# MULTIWII.net
KiCad netlist of a schematic drawn in EAGLE
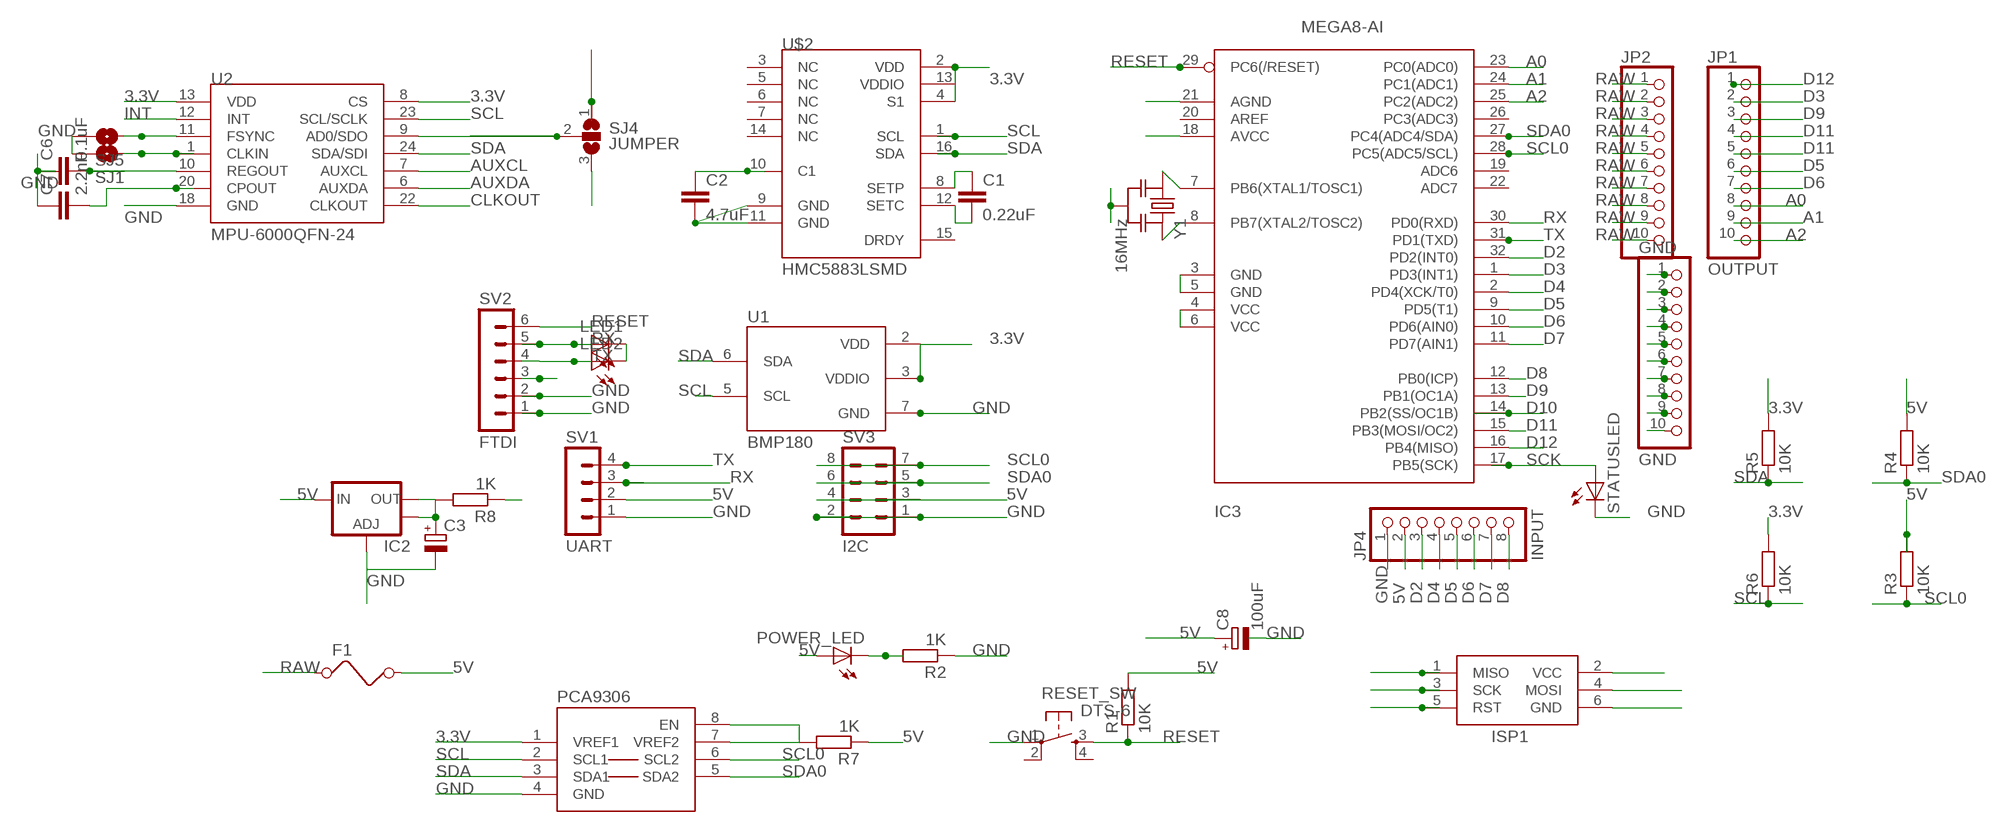
[diagram p0: schematic, sheet 1]

(export (version "E")
  (design (tool "Eeschema 10.0.6"))
  (components
    (comp (ref "C1")
      (value "0.22uF")
      (footprint "eagle-import:C0805")
      (libsource (lib "eagle-import") (part "C-EUC0805"))
    )
    (comp (ref "C2")
      (value "4.7uF")
      (footprint "eagle-import:C0805")
      (libsource (lib "eagle-import") (part "C-EUC0805"))
    )
    (comp (ref "C3")
      (value "CPOL-EUA/3216-18R")
      (footprint "eagle-import:A_3216-18R")
      (libsource (lib "eagle-import") (part "CPOL-EUA/3216-18R"))
    )
    (comp (ref "C6")
      (value "0.1uF")
      (footprint "eagle-import:C0805")
      (libsource (lib "eagle-import") (part "C-EUC0805"))
    )
    (comp (ref "C7")
      (value "2.2nF")
      (footprint "eagle-import:C0805")
      (libsource (lib "eagle-import") (part "C-EUC0805"))
    )
    (comp (ref "C8")
      (value "100uF")
      (footprint "eagle-import:CT7343")
      (libsource (lib "eagle-import") (part "CPOL-EUCT7343"))
    )
    (comp (ref "F1")
      (value "FUSEF")
      (footprint "eagle-import:1812")
      (libsource (lib "eagle-import") (part "FUSEF"))
    )
    (comp (ref "GND")
      (value "GND")
      (footprint "eagle-import:1X10")
      (libsource (lib "eagle-import") (part "PINHD-1X10"))
    )
    (comp (ref "IC2")
      (value "V_REG_LM1117SOT223")
      (footprint "eagle-import:SOT223")
      (libsource (lib "eagle-import") (part "V_REG_LM1117SOT223"))
    )
    (comp (ref "IC3")
      (value "MEGA8-AI")
      (footprint "eagle-import:TQFP32-08")
      (libsource (lib "eagle-import") (part "MEGA8-AI"))
    )
    (comp (ref "ISP1")
      (value "AVRISP-6")
      (footprint "eagle-import:AVRISP")
      (libsource (lib "eagle-import") (part "AVRISP-6"))
    )
    (comp (ref "JP1")
      (value "OUTPUT")
      (footprint "eagle-import:1X10")
      (libsource (lib "eagle-import") (part "PINHD-1X10"))
    )
    (comp (ref "JP2")
      (value "PINHD-1X10")
      (footprint "eagle-import:1X10")
      (libsource (lib "eagle-import") (part "PINHD-1X10"))
    )
    (comp (ref "JP4")
      (value "INPUT")
      (footprint "eagle-import:1X08")
      (libsource (lib "eagle-import") (part "PINHD-1X8"))
    )
    (comp (ref "LED1")
      (value "LEDCHIPLED_0805")
      (footprint "eagle-import:CHIPLED_0805")
      (libsource (lib "eagle-import") (part "LEDCHIPLED_0805"))
    )
    (comp (ref "LED2")
      (value "LEDCHIPLED_0805")
      (footprint "eagle-import:CHIPLED_0805")
      (libsource (lib "eagle-import") (part "LEDCHIPLED_0805"))
    )
    (comp (ref "PCA9306")
      (value "PCA9306")
      (footprint "eagle-import:PSOP-8")
      (libsource (lib "eagle-import") (part "PCA9306"))
    )
    (comp (ref "POWER_LED")
      (value "LEDCHIPLED_1206")
      (footprint "eagle-import:CHIPLED_1206")
      (libsource (lib "eagle-import") (part "LEDCHIPLED_1206"))
    )
    (comp (ref "R1")
      (value "10K")
      (footprint "eagle-import:M0805")
      (libsource (lib "eagle-import") (part "R-EU_M0805"))
    )
    (comp (ref "R2")
      (value "1K")
      (footprint "eagle-import:M0805")
      (libsource (lib "eagle-import") (part "R-EU_M0805"))
    )
    (comp (ref "R3")
      (value "10K")
      (footprint "eagle-import:M0805")
      (libsource (lib "eagle-import") (part "R-EU_M0805"))
    )
    (comp (ref "R4")
      (value "10K")
      (footprint "eagle-import:M0805")
      (libsource (lib "eagle-import") (part "R-EU_M0805"))
    )
    (comp (ref "R5")
      (value "10K")
      (footprint "eagle-import:M0805")
      (libsource (lib "eagle-import") (part "R-EU_M0805"))
    )
    (comp (ref "R6")
      (value "10K")
      (footprint "eagle-import:M0805")
      (libsource (lib "eagle-import") (part "R-EU_M0805"))
    )
    (comp (ref "R7")
      (value "1K")
      (footprint "eagle-import:M0805")
      (libsource (lib "eagle-import") (part "R-EU_M0805"))
    )
    (comp (ref "R8")
      (value "1K")
      (footprint "eagle-import:M0805")
      (libsource (lib "eagle-import") (part "R-EU_M0805"))
    )
    (comp (ref "RESET_SW")
      (value "DTS-6")
      (footprint "eagle-import:DTS-6")
      (libsource (lib "eagle-import") (part "DTS-6"))
    )
    (comp (ref "SJ1")
      (value "SOLDERJUMPERNC")
      (footprint "eagle-import:SJ_2S")
      (libsource (lib "eagle-import") (part "SOLDERJUMPERNC"))
    )
    (comp (ref "SJ4")
      (value "JUMPER")
      (footprint "eagle-import:SJ_2")
      (libsource (lib "eagle-import") (part "SJ2W"))
    )
    (comp (ref "SJ5")
      (value "SOLDERJUMPERNC")
      (footprint "eagle-import:SJ_2S")
      (libsource (lib "eagle-import") (part "SOLDERJUMPERNC"))
    )
    (comp (ref "STATUSLED")
      (value "LEDCHIP-LED0805")
      (footprint "eagle-import:CHIP-LED0805")
      (libsource (lib "eagle-import") (part "LEDCHIP-LED0805"))
    )
    (comp (ref "SV1")
      (value "UART")
      (footprint "eagle-import:MA04-1")
      (libsource (lib "eagle-import") (part "MA04-1"))
    )
    (comp (ref "SV2")
      (value "FTDI")
      (footprint "eagle-import:MA06-1")
      (libsource (lib "eagle-import") (part "MA06-1"))
    )
    (comp (ref "SV3")
      (value "I2C")
      (footprint "eagle-import:MA04-2")
      (libsource (lib "eagle-import") (part "MA04-2"))
    )
    (comp (ref "U$2")
      (value "HMC5883LSMD")
      (footprint "eagle-import:16LPCC")
      (libsource (lib "eagle-import") (part "HMC5883LSMD"))
    )
    (comp (ref "U1")
      (value "BMP180")
      (footprint "eagle-import:BMP180")
      (libsource (lib "eagle-import") (part "BMP180"))
    )
    (comp (ref "U2")
      (value "MPU-6000QFN-24")
      (footprint "eagle-import:QFN-24-TESTING")
      (libsource (lib "eagle-import") (part "MPU-6000QFN-24"))
    )
    (comp (ref "Y1")
      (value "16MHz")
      (footprint "eagle-import:RESONATOR_MURATA3")
      (libsource (lib "eagle-import") (part "RESONATOR-MURATACSTCR_G"))
    )
  )
  (nets
    (net (code "1") (name "3.3V") (class "Default")
      (node (ref "PCA9306") (pin "1") (pinfunction "VREF1_1") (pintype "bidirectional"))
      (node (ref "R5") (pin "2") (pinfunction "2_2") (pintype "passive"))
      (node (ref "R6") (pin "2") (pinfunction "2_2") (pintype "passive"))
      (node (ref "R8") (pin "1") (pinfunction "1_1") (pintype "passive"))
      (node (ref "SJ4") (pin "1") (pinfunction "1_1") (pintype "passive"))
      (node (ref "U$2") (pin "13") (pinfunction "VDDIO_13") (pintype "bidirectional"))
      (node (ref "U$2") (pin "2") (pinfunction "VDD_2") (pintype "bidirectional"))
      (node (ref "U$2") (pin "4") (pinfunction "S1_4") (pintype "bidirectional"))
      (node (ref "U1") (pin "2") (pinfunction "VDD_2") (pintype "power_in"))
      (node (ref "U1") (pin "3") (pinfunction "VDDIO_3") (pintype "power_in"))
      (node (ref "U2") (pin "13") (pinfunction "VDD_13") (pintype "bidirectional"))
      (node (ref "U2") (pin "8") (pinfunction "CS_8") (pintype "bidirectional"))
    )
    (net (code "2") (name "5V") (class "Default")
      (node (ref "C8") (pin "+") (pinfunction "+_+") (pintype "passive"))
      (node (ref "F1") (pin "2") (pinfunction "2_2") (pintype "passive"))
      (node (ref "IC2") (pin "3") (pinfunction "IN_3") (pintype "input"))
      (node (ref "IC3") (pin "18") (pinfunction "AVCC_18") (pintype "bidirectional"))
      (node (ref "IC3") (pin "4") (pinfunction "VCC_4") (pintype "bidirectional"))
      (node (ref "IC3") (pin "6") (pinfunction "VCC_6") (pintype "bidirectional"))
      (node (ref "ISP1") (pin "2") (pinfunction "VCC_2") (pintype "power_in"))
      (node (ref "JP4") (pin "2") (pinfunction "2_2") (pintype "passive"))
      (node (ref "POWER_LED") (pin "A") (pinfunction "A_A") (pintype "passive"))
      (node (ref "R1") (pin "2") (pinfunction "2_2") (pintype "passive"))
      (node (ref "R3") (pin "2") (pinfunction "2_2") (pintype "passive"))
      (node (ref "R4") (pin "2") (pinfunction "2_2") (pintype "passive"))
      (node (ref "R7") (pin "1") (pinfunction "1_1") (pintype "passive"))
      (node (ref "SV1") (pin "2") (pinfunction "2_2") (pintype "passive"))
      (node (ref "SV3") (pin "3") (pinfunction "3_3") (pintype "passive"))
      (node (ref "SV3") (pin "4") (pinfunction "4_4") (pintype "passive"))
    )
    (net (code "3") (name "A0") (class "Default")
      (node (ref "IC3") (pin "23") (pinfunction "PC0(ADC0)_23") (pintype "bidirectional"))
      (node (ref "JP1") (pin "8") (pinfunction "8_8") (pintype "passive"))
    )
    (net (code "4") (name "A1") (class "Default")
      (node (ref "IC3") (pin "24") (pinfunction "PC1(ADC1)_24") (pintype "bidirectional"))
      (node (ref "JP1") (pin "9") (pinfunction "9_9") (pintype "passive"))
    )
    (net (code "5") (name "A2") (class "Default")
      (node (ref "IC3") (pin "25") (pinfunction "PC2(ADC2)_25") (pintype "bidirectional"))
      (node (ref "JP1") (pin "10") (pinfunction "10_10") (pintype "passive"))
    )
    (net (code "6") (name "AUXCL") (class "Default")
      (node (ref "U2") (pin "7") (pinfunction "AUXCL_7") (pintype "bidirectional"))
    )
    (net (code "7") (name "AUXDA") (class "Default")
      (node (ref "U2") (pin "6") (pinfunction "AUXDA_6") (pintype "bidirectional"))
    )
    (net (code "8") (name "CLKOUT") (class "Default")
      (node (ref "U2") (pin "22") (pinfunction "CLKOUT_22") (pintype "bidirectional"))
    )
    (net (code "9") (name "D2") (class "Default")
      (node (ref "IC3") (pin "32") (pinfunction "PD2(INT0)_32") (pintype "bidirectional"))
      (node (ref "JP4") (pin "3") (pinfunction "3_3") (pintype "passive"))
    )
    (net (code "10") (name "D3") (class "Default")
      (node (ref "IC3") (pin "1") (pinfunction "PD3(INT1)_1") (pintype "bidirectional"))
      (node (ref "JP1") (pin "2") (pinfunction "2_2") (pintype "passive"))
    )
    (net (code "11") (name "D4") (class "Default")
      (node (ref "IC3") (pin "2") (pinfunction "PD4(XCK/T0)_2") (pintype "bidirectional"))
      (node (ref "JP4") (pin "4") (pinfunction "4_4") (pintype "passive"))
    )
    (net (code "12") (name "D5") (class "Default")
      (node (ref "IC3") (pin "9") (pinfunction "PD5(T1)_9") (pintype "bidirectional"))
      (node (ref "JP1") (pin "6") (pinfunction "6_6") (pintype "passive"))
      (node (ref "JP4") (pin "5") (pinfunction "5_5") (pintype "passive"))
    )
    (net (code "13") (name "D6") (class "Default")
      (node (ref "IC3") (pin "10") (pinfunction "PD6(AIN0)_10") (pintype "bidirectional"))
      (node (ref "JP1") (pin "7") (pinfunction "7_7") (pintype "passive"))
      (node (ref "JP4") (pin "6") (pinfunction "6_6") (pintype "passive"))
    )
    (net (code "14") (name "D7") (class "Default")
      (node (ref "IC3") (pin "11") (pinfunction "PD7(AIN1)_11") (pintype "bidirectional"))
      (node (ref "JP4") (pin "7") (pinfunction "7_7") (pintype "passive"))
    )
    (net (code "15") (name "D8") (class "Default")
      (node (ref "IC3") (pin "12") (pinfunction "PB0(ICP)_12") (pintype "bidirectional"))
      (node (ref "JP4") (pin "8") (pinfunction "8_8") (pintype "passive"))
    )
    (net (code "16") (name "D9") (class "Default")
      (node (ref "IC3") (pin "13") (pinfunction "PB1(OC1A)_13") (pintype "bidirectional"))
      (node (ref "JP1") (pin "3") (pinfunction "3_3") (pintype "passive"))
    )
    (net (code "17") (name "D10") (class "Default")
      (node (ref "IC3") (pin "14") (pinfunction "PB2(SS/OC1B)_14") (pintype "bidirectional"))
      (node (ref "JP1") (pin "4") (pinfunction "4_4") (pintype "passive"))
    )
    (net (code "18") (name "D11") (class "Default")
      (node (ref "IC3") (pin "15") (pinfunction "PB3(MOSI/OC2)_15") (pintype "bidirectional"))
      (node (ref "ISP1") (pin "4") (pinfunction "MOSI_4") (pintype "output"))
      (node (ref "JP1") (pin "5") (pinfunction "5_5") (pintype "passive"))
    )
    (net (code "19") (name "D12") (class "Default")
      (node (ref "IC3") (pin "16") (pinfunction "PB4(MISO)_16") (pintype "bidirectional"))
      (node (ref "ISP1") (pin "1") (pinfunction "MISO_1") (pintype "input"))
      (node (ref "JP1") (pin "1") (pinfunction "1_1") (pintype "passive"))
    )
    (net (code "20") (name "GND") (class "Default")
      (node (ref "C2") (pin "2") (pinfunction "2_2") (pintype "passive"))
      (node (ref "C3") (pin "-") (pinfunction "-_-") (pintype "passive"))
      (node (ref "C6") (pin "1") (pinfunction "1_1") (pintype "passive"))
      (node (ref "C7") (pin "1") (pinfunction "1_1") (pintype "passive"))
      (node (ref "C8") (pin "-") (pinfunction "-_-") (pintype "passive"))
      (node (ref "GND") (pin "1") (pinfunction "1_1") (pintype "passive"))
      (node (ref "GND") (pin "10") (pinfunction "10_10") (pintype "passive"))
      (node (ref "GND") (pin "2") (pinfunction "2_2") (pintype "passive"))
      (node (ref "GND") (pin "3") (pinfunction "3_3") (pintype "passive"))
      (node (ref "GND") (pin "4") (pinfunction "4_4") (pintype "passive"))
      (node (ref "GND") (pin "5") (pinfunction "5_5") (pintype "passive"))
      (node (ref "GND") (pin "6") (pinfunction "6_6") (pintype "passive"))
      (node (ref "GND") (pin "7") (pinfunction "7_7") (pintype "passive"))
      (node (ref "GND") (pin "8") (pinfunction "8_8") (pintype "passive"))
      (node (ref "GND") (pin "9") (pinfunction "9_9") (pintype "passive"))
      (node (ref "IC2") (pin "1") (pinfunction "ADJ_1") (pintype "input"))
      (node (ref "IC3") (pin "21") (pinfunction "AGND_21") (pintype "bidirectional"))
      (node (ref "IC3") (pin "3") (pinfunction "GND_3") (pintype "bidirectional"))
      (node (ref "IC3") (pin "5") (pinfunction "GND_5") (pintype "bidirectional"))
      (node (ref "ISP1") (pin "6") (pinfunction "GND_6") (pintype "power_in"))
      (node (ref "JP4") (pin "1") (pinfunction "1_1") (pintype "passive"))
      (node (ref "LED1") (pin "C") (pinfunction "C_C") (pintype "passive"))
      (node (ref "LED2") (pin "C") (pinfunction "C_C") (pintype "passive"))
      (node (ref "PCA9306") (pin "4") (pinfunction "GND_4") (pintype "bidirectional"))
      (node (ref "R2") (pin "1") (pinfunction "1_1") (pintype "passive"))
      (node (ref "RESET_SW") (pin "1") (pinfunction "1_1") (pintype "passive"))
      (node (ref "SJ1") (pin "2") (pinfunction "2_2") (pintype "passive"))
      (node (ref "SJ4") (pin "3") (pinfunction "3_3") (pintype "passive"))
      (node (ref "SJ5") (pin "2") (pinfunction "2_2") (pintype "passive"))
      (node (ref "STATUSLED") (pin "C") (pinfunction "C_C") (pintype "passive"))
      (node (ref "SV1") (pin "1") (pinfunction "1_1") (pintype "passive"))
      (node (ref "SV2") (pin "1") (pinfunction "1_1") (pintype "passive"))
      (node (ref "SV2") (pin "2") (pinfunction "2_2") (pintype "passive"))
      (node (ref "SV3") (pin "1") (pinfunction "1_1") (pintype "passive"))
      (node (ref "SV3") (pin "2") (pinfunction "2_2") (pintype "passive"))
      (node (ref "U$2") (pin "11") (pinfunction "GND_11") (pintype "bidirectional"))
      (node (ref "U$2") (pin "9") (pinfunction "GND_9") (pintype "bidirectional"))
      (node (ref "U1") (pin "7") (pinfunction "GND_7") (pintype "power_in"))
      (node (ref "U2") (pin "18") (pinfunction "GND_18") (pintype "bidirectional"))
      (node (ref "Y1") (pin "2") (pinfunction "2_2") (pintype "passive"))
    )
    (net (code "21") (name "INT") (class "Default")
      (node (ref "U2") (pin "12") (pinfunction "INT_12") (pintype "bidirectional"))
    )
    (net (code "22") (name "Net-(C3-Pad+)") (class "Default")
      (node (ref "C3") (pin "+") (pinfunction "+_+") (pintype "passive"))
      (node (ref "IC2") (pin "2") (pinfunction "OUT_2") (pintype "output"))
      (node (ref "IC2") (pin "4") (pinfunction "OUT_4") (pintype "output"))
      (node (ref "R8") (pin "2") (pinfunction "2_2") (pintype "passive"))
    )
    (net (code "23") (name "Net-(IC3-PB6(XTAL1{slash}TOSC1))") (class "Default")
      (node (ref "IC3") (pin "7") (pinfunction "PB6(XTAL1/TOSC1)_7") (pintype "bidirectional"))
      (node (ref "Y1") (pin "1") (pinfunction "1_1") (pintype "passive"))
    )
    (net (code "24") (name "Net-(IC3-PB7(XTAL2{slash}TOSC2))") (class "Default")
      (node (ref "IC3") (pin "8") (pinfunction "PB7(XTAL2/TOSC2)_8") (pintype "bidirectional"))
      (node (ref "Y1") (pin "3") (pinfunction "3_3") (pintype "passive"))
    )
    (net (code "25") (name "Net-(PCA9306-EN)") (class "Default")
      (node (ref "PCA9306") (pin "7") (pinfunction "VREF2_7") (pintype "bidirectional"))
      (node (ref "PCA9306") (pin "8") (pinfunction "EN_8") (pintype "bidirectional"))
      (node (ref "R7") (pin "2") (pinfunction "2_2") (pintype "passive"))
    )
    (net (code "26") (name "Net-(POWER_LED-PadC)") (class "Default")
      (node (ref "POWER_LED") (pin "C") (pinfunction "C_C") (pintype "passive"))
      (node (ref "R2") (pin "2") (pinfunction "2_2") (pintype "passive"))
    )
    (net (code "27") (name "Net-(U$2-C1)") (class "Default")
      (node (ref "C2") (pin "1") (pinfunction "1_1") (pintype "passive"))
      (node (ref "U$2") (pin "10") (pinfunction "C1_10") (pintype "bidirectional"))
    )
    (net (code "28") (name "Net-(U$2-SETC)") (class "Default")
      (node (ref "C1") (pin "2") (pinfunction "2_2") (pintype "passive"))
      (node (ref "U$2") (pin "12") (pinfunction "SETC_12") (pintype "bidirectional"))
    )
    (net (code "29") (name "Net-(U$2-SETP)") (class "Default")
      (node (ref "C1") (pin "1") (pinfunction "1_1") (pintype "passive"))
      (node (ref "U$2") (pin "8") (pinfunction "SETP_8") (pintype "bidirectional"))
    )
    (net (code "30") (name "Net-(U2-AD0{slash}SDO)") (class "Default")
      (node (ref "SJ4") (pin "2") (pinfunction "2_2") (pintype "passive"))
      (node (ref "U2") (pin "9") (pinfunction "AD0/SDO_9") (pintype "bidirectional"))
    )
    (net (code "31") (name "Net-(U2-CLKIN)") (class "Default")
      (node (ref "SJ1") (pin "1") (pinfunction "1_1") (pintype "passive"))
      (node (ref "U2") (pin "1") (pinfunction "CLKIN_1") (pintype "bidirectional"))
    )
    (net (code "32") (name "Net-(U2-CPOUT)") (class "Default")
      (node (ref "C7") (pin "2") (pinfunction "2_2") (pintype "passive"))
      (node (ref "U2") (pin "20") (pinfunction "CPOUT_20") (pintype "bidirectional"))
    )
    (net (code "33") (name "Net-(U2-FSYNC)") (class "Default")
      (node (ref "SJ5") (pin "1") (pinfunction "1_1") (pintype "passive"))
      (node (ref "U2") (pin "11") (pinfunction "FSYNC_11") (pintype "bidirectional"))
    )
    (net (code "34") (name "Net-(U2-REGOUT)") (class "Default")
      (node (ref "C6") (pin "2") (pinfunction "2_2") (pintype "passive"))
      (node (ref "U2") (pin "10") (pinfunction "REGOUT_10") (pintype "bidirectional"))
    )
    (net (code "35") (name "RAW") (class "Default")
      (node (ref "F1") (pin "1") (pinfunction "1_1") (pintype "passive"))
      (node (ref "JP2") (pin "1") (pinfunction "1_1") (pintype "passive"))
      (node (ref "JP2") (pin "10") (pinfunction "10_10") (pintype "passive"))
      (node (ref "JP2") (pin "2") (pinfunction "2_2") (pintype "passive"))
      (node (ref "JP2") (pin "3") (pinfunction "3_3") (pintype "passive"))
      (node (ref "JP2") (pin "4") (pinfunction "4_4") (pintype "passive"))
      (node (ref "JP2") (pin "5") (pinfunction "5_5") (pintype "passive"))
      (node (ref "JP2") (pin "6") (pinfunction "6_6") (pintype "passive"))
      (node (ref "JP2") (pin "7") (pinfunction "7_7") (pintype "passive"))
      (node (ref "JP2") (pin "8") (pinfunction "8_8") (pintype "passive"))
      (node (ref "JP2") (pin "9") (pinfunction "9_9") (pintype "passive"))
      (node (ref "SV2") (pin "3") (pinfunction "3_3") (pintype "passive"))
    )
    (net (code "36") (name "RESET") (class "Default")
      (node (ref "IC3") (pin "29") (pinfunction "PC6(/RESET)_29") (pintype "bidirectional"))
      (node (ref "ISP1") (pin "5") (pinfunction "RST_5") (pintype "output"))
      (node (ref "R1") (pin "1") (pinfunction "1_1") (pintype "passive"))
      (node (ref "RESET_SW") (pin "3") (pinfunction "3_3") (pintype "passive"))
      (node (ref "SV2") (pin "6") (pinfunction "6_6") (pintype "passive"))
    )
    (net (code "37") (name "RX") (class "Default")
      (node (ref "IC3") (pin "30") (pinfunction "PD0(RXD)_30") (pintype "bidirectional"))
      (node (ref "LED1") (pin "A") (pinfunction "A_A") (pintype "passive"))
      (node (ref "SV1") (pin "3") (pinfunction "3_3") (pintype "passive"))
      (node (ref "SV2") (pin "5") (pinfunction "5_5") (pintype "passive"))
    )
    (net (code "38") (name "SCK") (class "Default")
      (node (ref "IC3") (pin "17") (pinfunction "PB5(SCK)_17") (pintype "bidirectional"))
      (node (ref "ISP1") (pin "3") (pinfunction "SCK_3") (pintype "output"))
      (node (ref "STATUSLED") (pin "A") (pinfunction "A_A") (pintype "passive"))
    )
    (net (code "39") (name "SCL") (class "Default")
      (node (ref "PCA9306") (pin "2") (pinfunction "SCL1_2") (pintype "bidirectional"))
      (node (ref "R6") (pin "1") (pinfunction "1_1") (pintype "passive"))
      (node (ref "U$2") (pin "1") (pinfunction "SCL_1") (pintype "bidirectional"))
      (node (ref "U1") (pin "5") (pinfunction "SCL_5") (pintype "input"))
      (node (ref "U2") (pin "23") (pinfunction "SCL/SCLK_23") (pintype "bidirectional"))
    )
    (net (code "40") (name "SCL0") (class "Default")
      (node (ref "IC3") (pin "28") (pinfunction "PC5(ADC5/SCL)_28") (pintype "bidirectional"))
      (node (ref "PCA9306") (pin "6") (pinfunction "SCL2_6") (pintype "bidirectional"))
      (node (ref "R3") (pin "1") (pinfunction "1_1") (pintype "passive"))
      (node (ref "SV3") (pin "7") (pinfunction "7_7") (pintype "passive"))
      (node (ref "SV3") (pin "8") (pinfunction "8_8") (pintype "passive"))
    )
    (net (code "41") (name "SDA") (class "Default")
      (node (ref "PCA9306") (pin "3") (pinfunction "SDA1_3") (pintype "bidirectional"))
      (node (ref "R5") (pin "1") (pinfunction "1_1") (pintype "passive"))
      (node (ref "U$2") (pin "16") (pinfunction "SDA_16") (pintype "bidirectional"))
      (node (ref "U1") (pin "6") (pinfunction "SDA_6") (pintype "bidirectional"))
      (node (ref "U2") (pin "24") (pinfunction "SDA/SDI_24") (pintype "bidirectional"))
    )
    (net (code "42") (name "SDA0") (class "Default")
      (node (ref "IC3") (pin "27") (pinfunction "PC4(ADC4/SDA)_27") (pintype "bidirectional"))
      (node (ref "PCA9306") (pin "5") (pinfunction "SDA2_5") (pintype "bidirectional"))
      (node (ref "R4") (pin "1") (pinfunction "1_1") (pintype "passive"))
      (node (ref "SV3") (pin "5") (pinfunction "5_5") (pintype "passive"))
      (node (ref "SV3") (pin "6") (pinfunction "6_6") (pintype "passive"))
    )
    (net (code "43") (name "TX") (class "Default")
      (node (ref "IC3") (pin "31") (pinfunction "PD1(TXD)_31") (pintype "bidirectional"))
      (node (ref "LED2") (pin "A") (pinfunction "A_A") (pintype "passive"))
      (node (ref "SV1") (pin "4") (pinfunction "4_4") (pintype "passive"))
      (node (ref "SV2") (pin "4") (pinfunction "4_4") (pintype "passive"))
    )
    (net (code "44") (name "unconnected-(IC3-ADC6-Pad19)") (class "Default")
      (node (ref "IC3") (pin "19") (pinfunction "ADC6_19") (pintype "bidirectional"))
    )
    (net (code "45") (name "unconnected-(IC3-ADC7-Pad22)") (class "Default")
      (node (ref "IC3") (pin "22") (pinfunction "ADC7_22") (pintype "bidirectional"))
    )
    (net (code "46") (name "unconnected-(IC3-AREF-Pad20)") (class "Default")
      (node (ref "IC3") (pin "20") (pinfunction "AREF_20") (pintype "bidirectional"))
    )
    (net (code "47") (name "unconnected-(IC3-PC3(ADC3)-Pad26)") (class "Default")
      (node (ref "IC3") (pin "26") (pinfunction "PC3(ADC3)_26") (pintype "bidirectional"))
    )
    (net (code "48") (name "unconnected-(RESET_SW-Pad2)") (class "Default")
      (node (ref "RESET_SW") (pin "2") (pinfunction "2_2") (pintype "passive"))
    )
    (net (code "49") (name "unconnected-(RESET_SW-Pad4)") (class "Default")
      (node (ref "RESET_SW") (pin "4") (pinfunction "4_4") (pintype "passive"))
    )
    (net (code "50") (name "unconnected-(U$2-DRDY-Pad15)") (class "Default")
      (node (ref "U$2") (pin "15") (pinfunction "DRDY_15") (pintype "bidirectional"))
    )
    (net (code "51") (name "unconnected-(U$2-NC-Pad3)") (class "Default")
      (node (ref "U$2") (pin "3") (pinfunction "NC_3") (pintype "bidirectional"))
    )
    (net (code "52") (name "unconnected-(U$2-NC-Pad5)") (class "Default")
      (node (ref "U$2") (pin "5") (pinfunction "NC_5") (pintype "bidirectional"))
    )
    (net (code "53") (name "unconnected-(U$2-NC-Pad6)") (class "Default")
      (node (ref "U$2") (pin "6") (pinfunction "NC_6") (pintype "bidirectional"))
    )
    (net (code "54") (name "unconnected-(U$2-NC-Pad7)") (class "Default")
      (node (ref "U$2") (pin "7") (pinfunction "NC_7") (pintype "bidirectional"))
    )
    (net (code "55") (name "unconnected-(U$2-NC-Pad14)") (class "Default")
      (node (ref "U$2") (pin "14") (pinfunction "NC_14") (pintype "bidirectional"))
    )
  )
)
